# 4.net
KiCad netlist of a schematic drawn in EAGLE
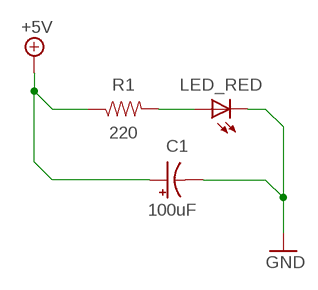
[diagram p0: schematic, sheet 1]
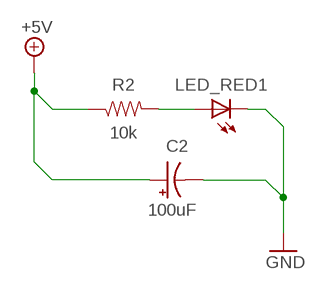
[diagram p1: schematic, sheet 2]
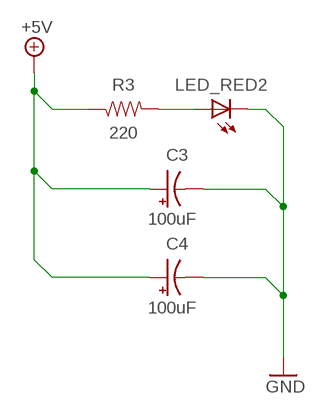
[diagram p2: schematic, sheet 3]

(export (version "E")
  (design (tool "Eeschema 10.0.6"))
  (components
    (comp (ref "C3")
      (value "100uF")
      (footprint "eagle-import:CPOL-RADIAL-2.5MM-6.5MM")
      (libsource (lib "eagle-import") (part "100UF-POLAR-RADIAL-2.5MM-25V-20%"))
    )
    (comp (ref "C4")
      (value "100uF")
      (footprint "eagle-import:CPOL-RADIAL-2.5MM-6.5MM")
      (libsource (lib "eagle-import") (part "100UF-POLAR-RADIAL-2.5MM-25V-20%"))
    )
    (comp (ref "LED_RED2")
      (value "LED5MM")
      (footprint "eagle-import:LED5MM")
      (libsource (lib "eagle-import") (part "LED5MM"))
    )
    (comp (ref "R3")
      (value "220")
      (footprint "eagle-import:AXIAL-0.3")
      (libsource (lib "eagle-import") (part "100OHM-HORIZ-1/4W-1%"))
    )
    (comp (ref "C1")
      (value "100uF")
      (footprint "eagle-import:CPOL-RADIAL-2.5MM-6.5MM")
      (libsource (lib "eagle-import") (part "100UF-POLAR-RADIAL-2.5MM-25V-20%"))
    )
    (comp (ref "LED_RED")
      (value "LED5MM")
      (footprint "eagle-import:LED5MM")
      (libsource (lib "eagle-import") (part "LED5MM"))
    )
    (comp (ref "R1")
      (value "220")
      (footprint "eagle-import:AXIAL-0.3")
      (libsource (lib "eagle-import") (part "100OHM-HORIZ-1/4W-1%"))
    )
    (comp (ref "C2")
      (value "100uF")
      (footprint "eagle-import:CPOL-RADIAL-2.5MM-6.5MM")
      (libsource (lib "eagle-import") (part "100UF-POLAR-RADIAL-2.5MM-25V-20%"))
    )
    (comp (ref "LED_RED1")
      (value "LED5MM")
      (footprint "eagle-import:LED5MM")
      (libsource (lib "eagle-import") (part "LED5MM"))
    )
    (comp (ref "R2")
      (value "10k")
      (footprint "eagle-import:AXIAL-0.3")
      (libsource (lib "eagle-import") (part "100OHM-HORIZ-1/4W-1%"))
    )
  )
  (nets
    (net (code "1") (name "+5V") (class "Default")
      (node (ref "C1") (pin "1") (pinfunction "+_1") (pintype "passive"))
      (node (ref "C2") (pin "1") (pinfunction "+_1") (pintype "passive"))
      (node (ref "C3") (pin "1") (pinfunction "+_1") (pintype "passive"))
      (node (ref "C4") (pin "1") (pinfunction "+_1") (pintype "passive"))
      (node (ref "R1") (pin "P$1") (pinfunction "1_P$1") (pintype "passive"))
      (node (ref "R2") (pin "P$1") (pinfunction "1_P$1") (pintype "passive"))
      (node (ref "R3") (pin "P$1") (pinfunction "1_P$1") (pintype "passive"))
    )
    (net (code "2") (name "GND") (class "Default")
      (node (ref "C1") (pin "2") (pinfunction "-_2") (pintype "passive"))
      (node (ref "C2") (pin "2") (pinfunction "-_2") (pintype "passive"))
      (node (ref "C3") (pin "2") (pinfunction "-_2") (pintype "passive"))
      (node (ref "C4") (pin "2") (pinfunction "-_2") (pintype "passive"))
      (node (ref "LED_RED") (pin "K") (pinfunction "C_K") (pintype "passive"))
      (node (ref "LED_RED1") (pin "K") (pinfunction "C_K") (pintype "passive"))
      (node (ref "LED_RED2") (pin "K") (pinfunction "C_K") (pintype "passive"))
    )
    (net (code "3") (name "Net-(R1-2)") (class "Default")
      (node (ref "LED_RED") (pin "A") (pinfunction "A_A") (pintype "passive"))
      (node (ref "R1") (pin "P$2") (pinfunction "2_P$2") (pintype "passive"))
    )
    (net (code "4") (name "Net-(R2-2)") (class "Default")
      (node (ref "LED_RED1") (pin "A") (pinfunction "A_A") (pintype "passive"))
      (node (ref "R2") (pin "P$2") (pinfunction "2_P$2") (pintype "passive"))
    )
    (net (code "5") (name "Net-(R3-2)") (class "Default")
      (node (ref "LED_RED2") (pin "A") (pinfunction "A_A") (pintype "passive"))
      (node (ref "R3") (pin "P$2") (pinfunction "2_P$2") (pintype "passive"))
    )
  )
)
